# MotorControllerMainBoard.net
KiCad netlist of a schematic drawn in EAGLE
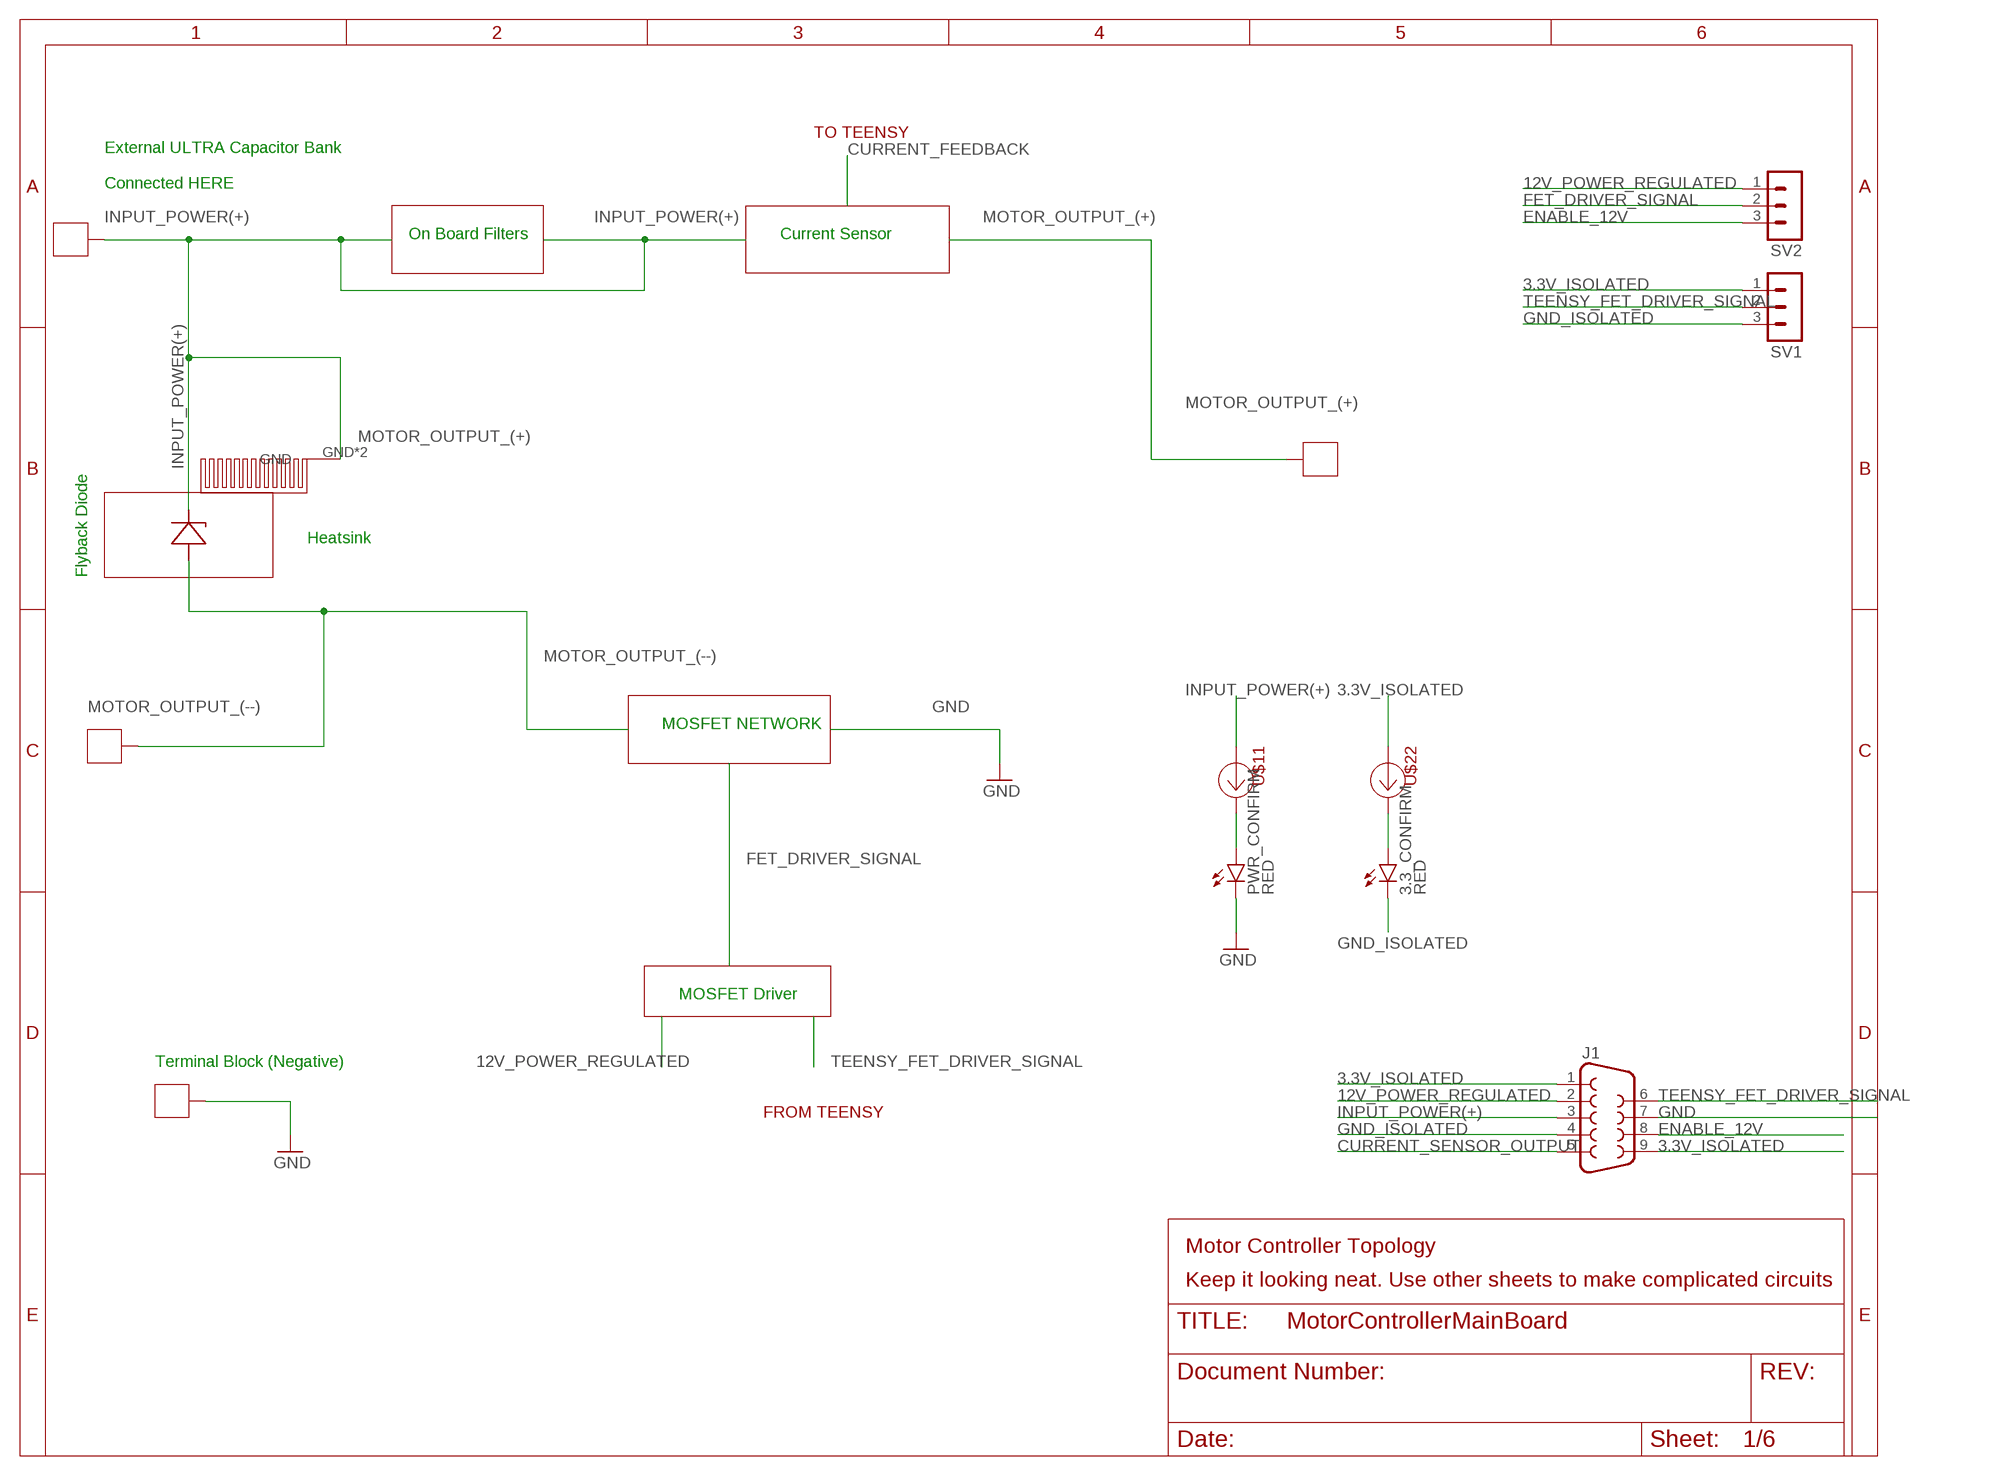
[diagram p0: schematic, sheet 1]
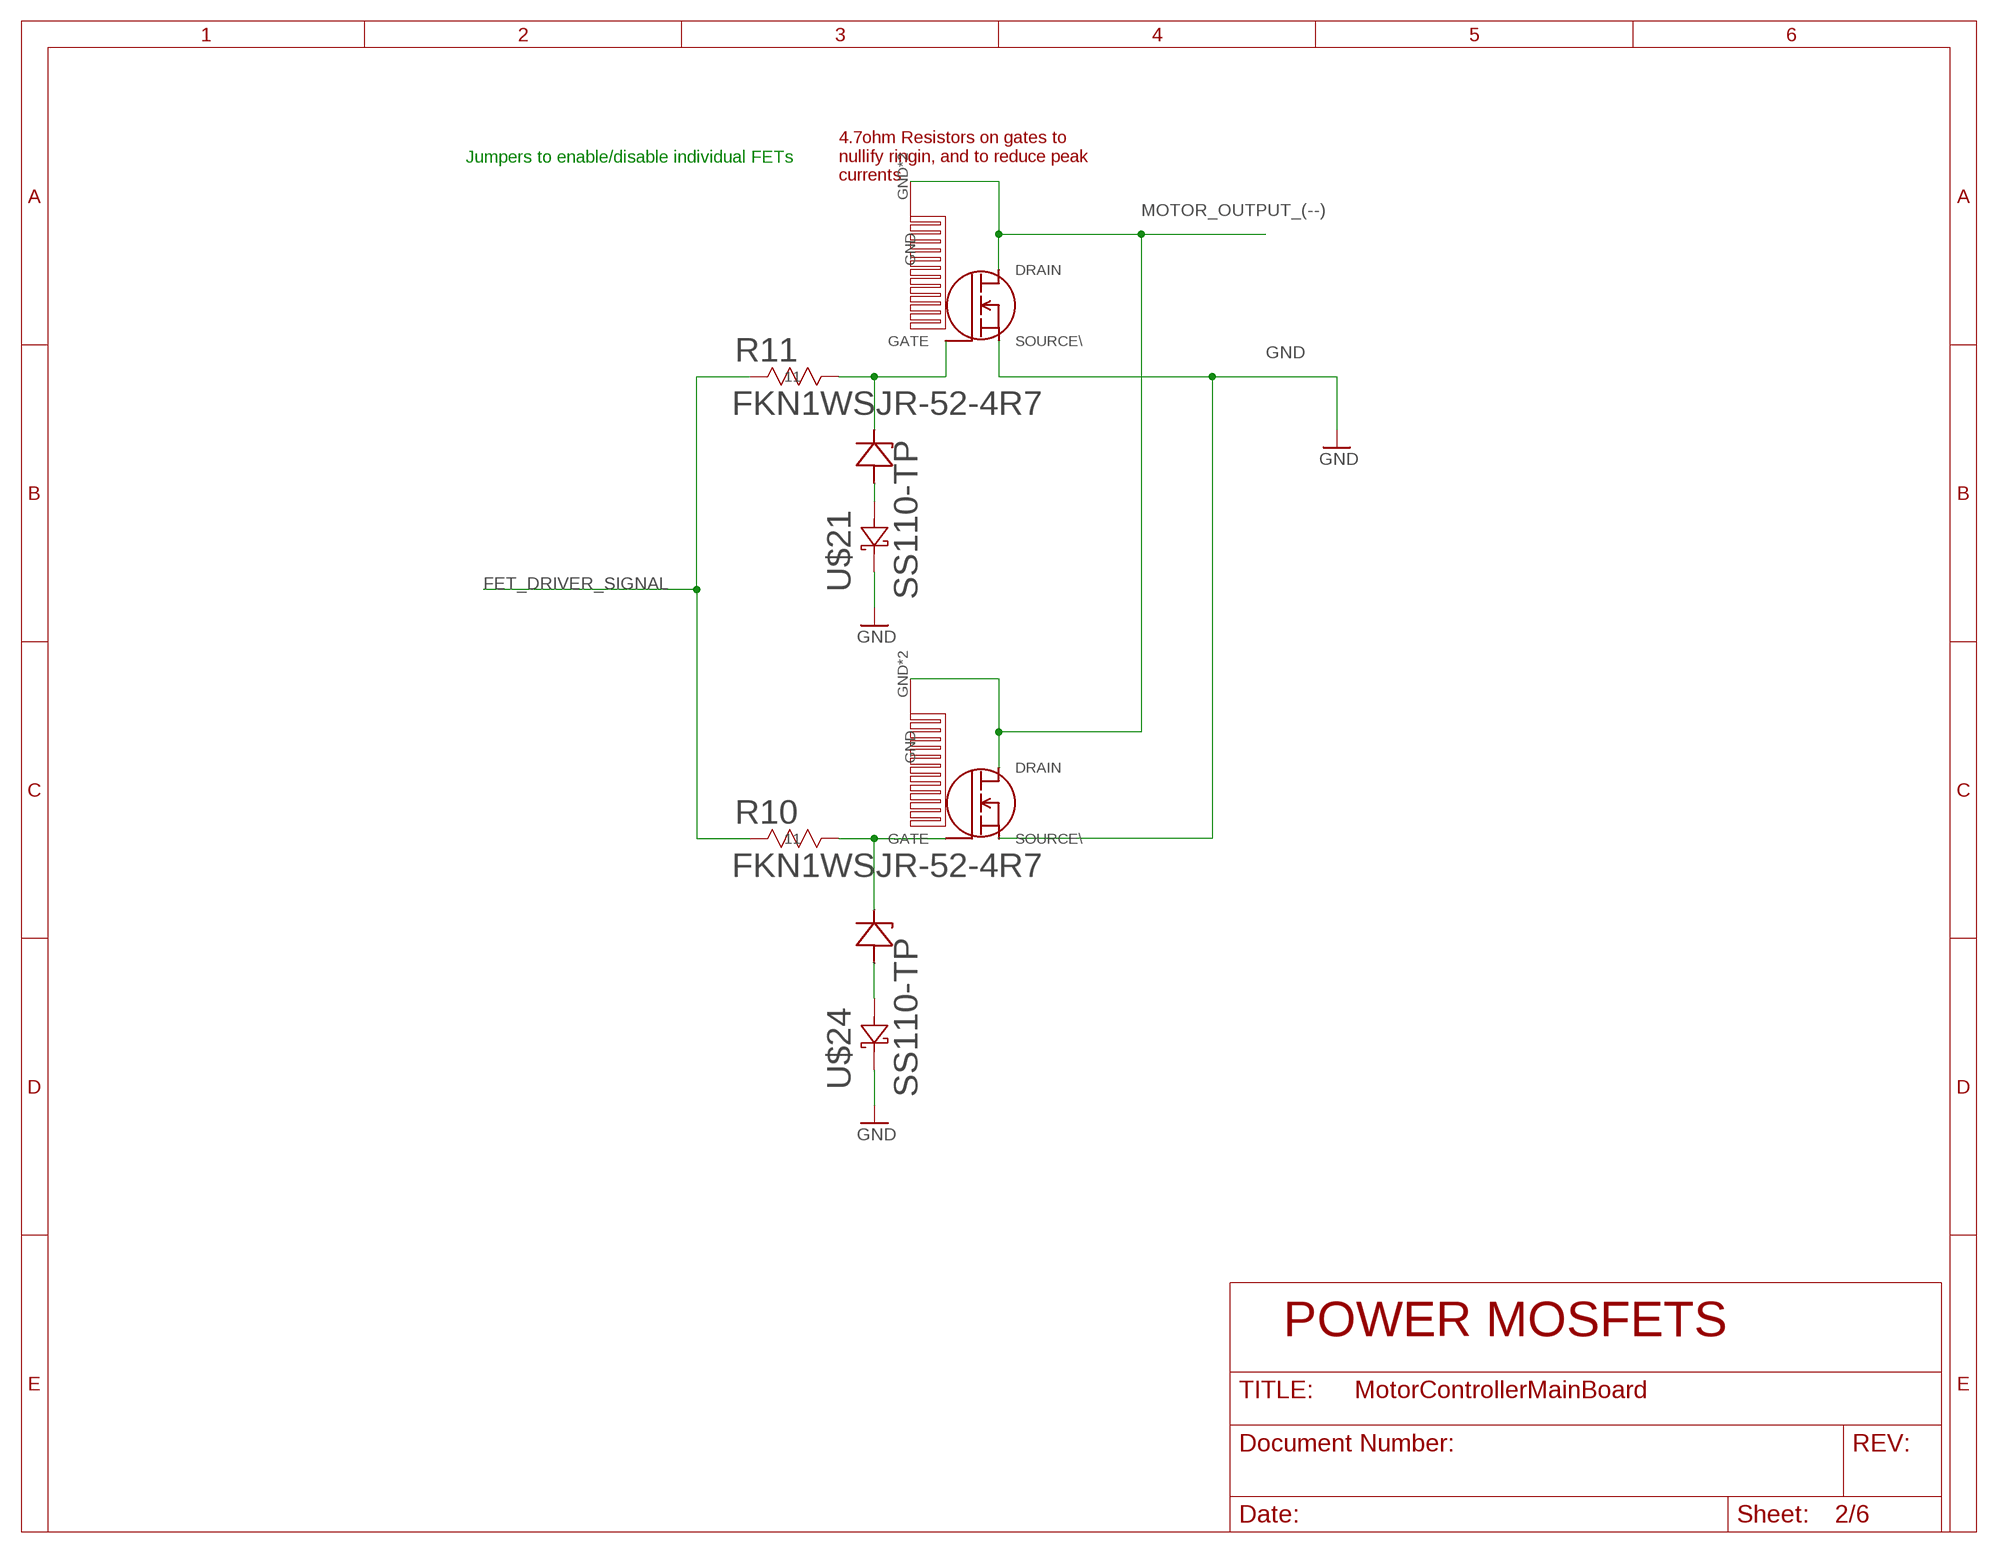
[diagram p1: schematic, sheet 2]
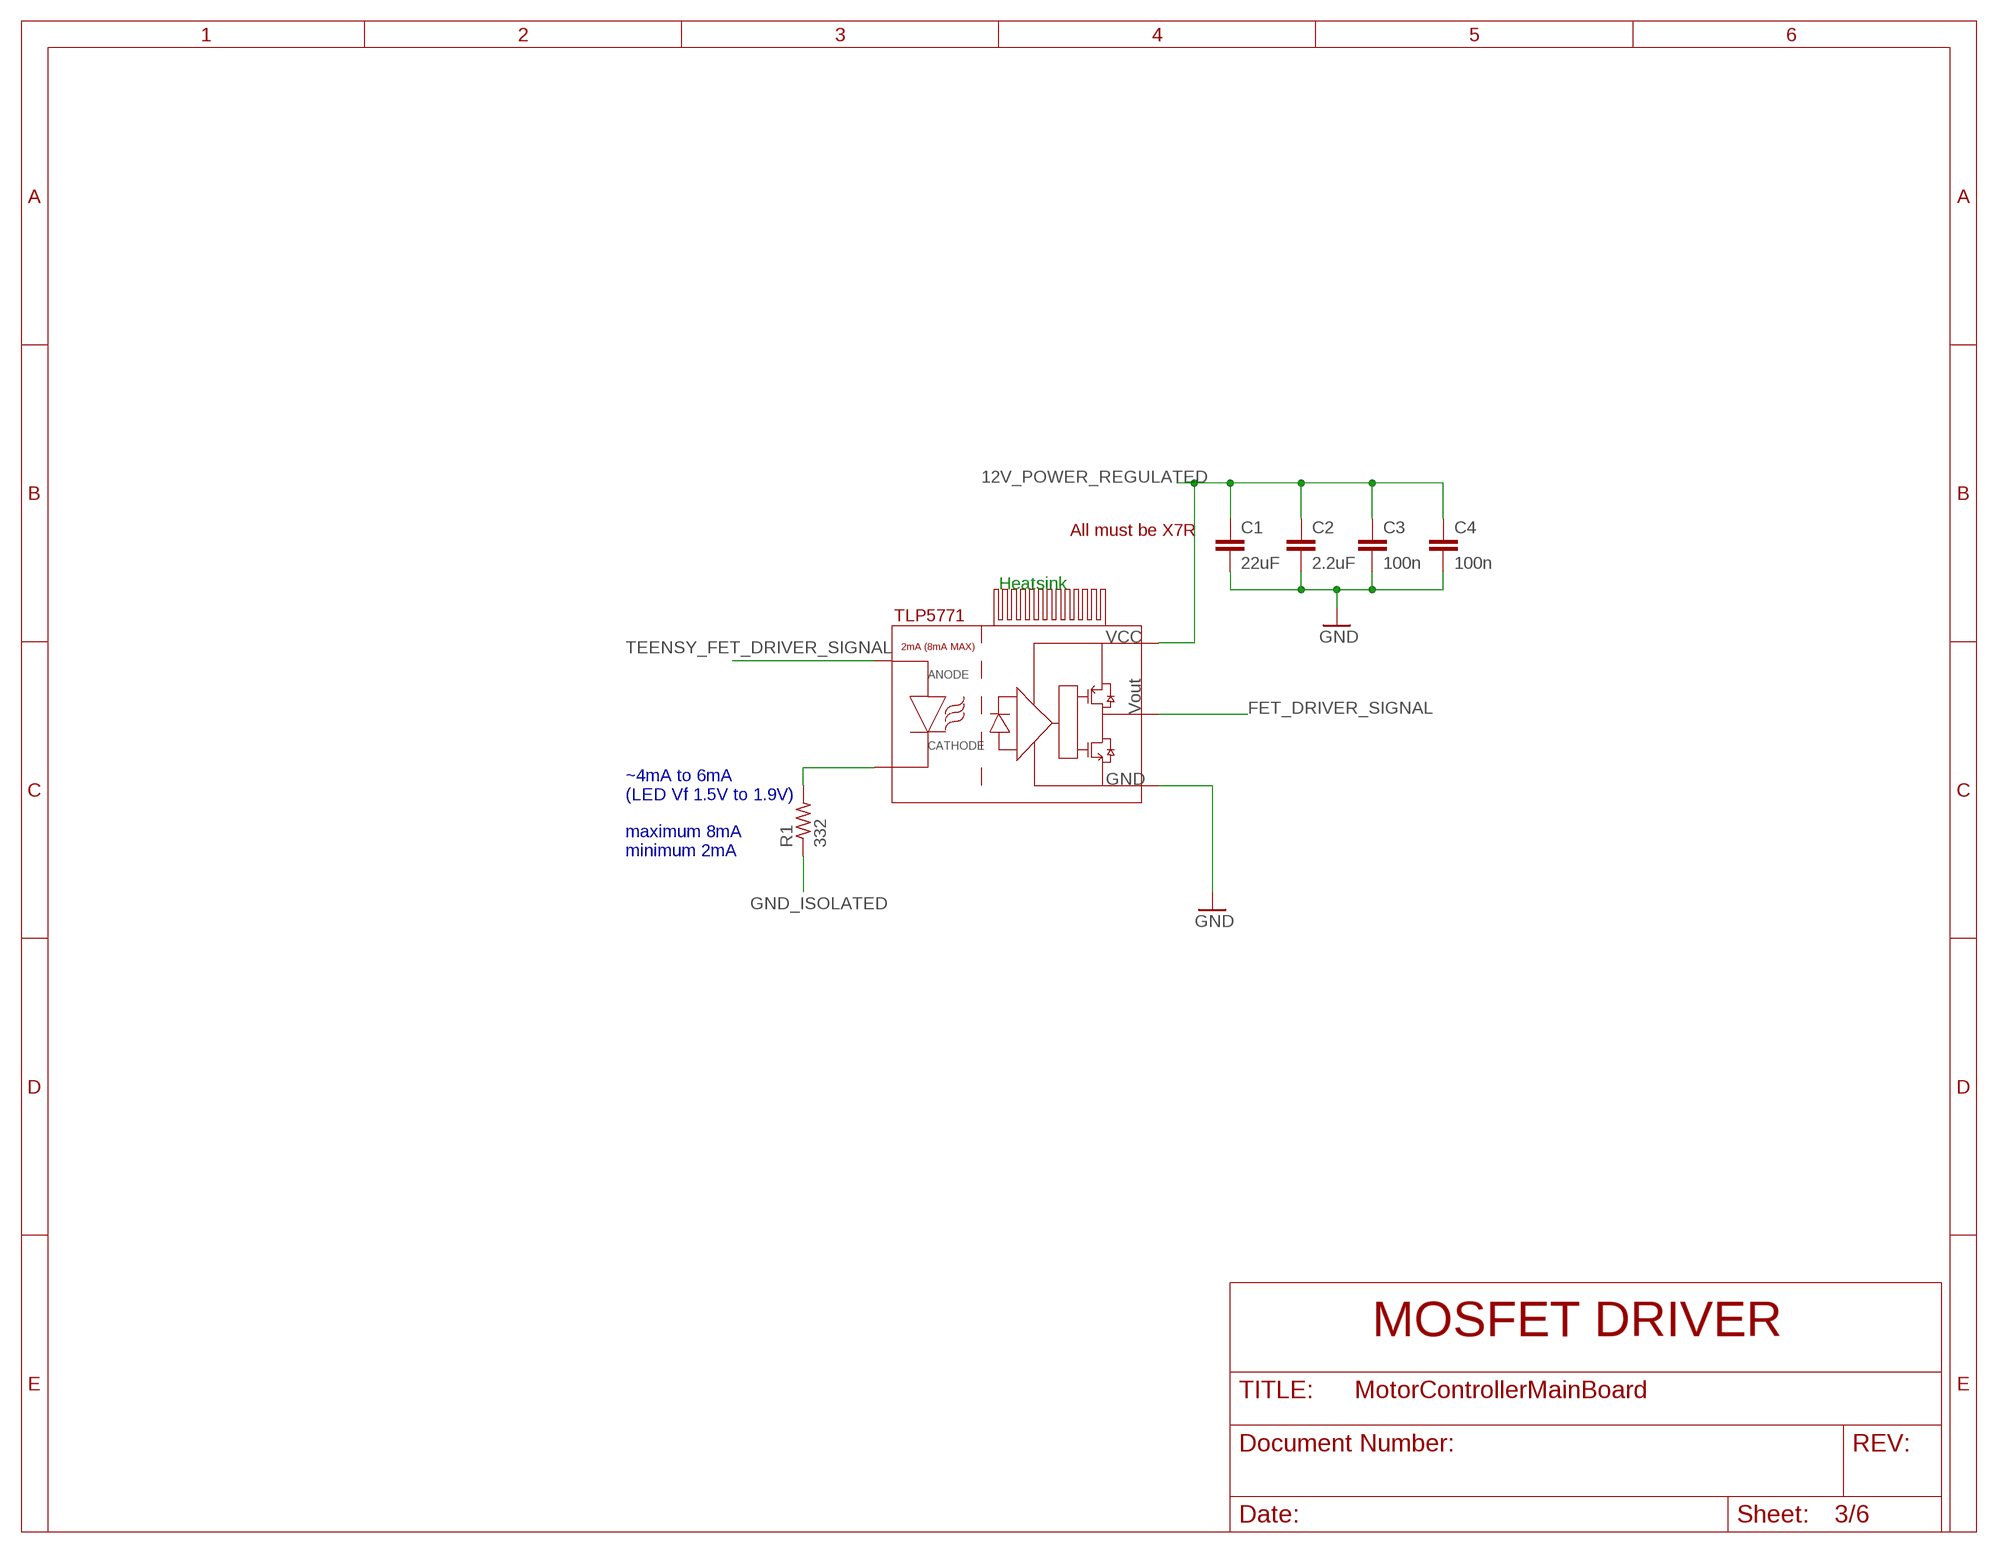
[diagram p2: schematic, sheet 3]
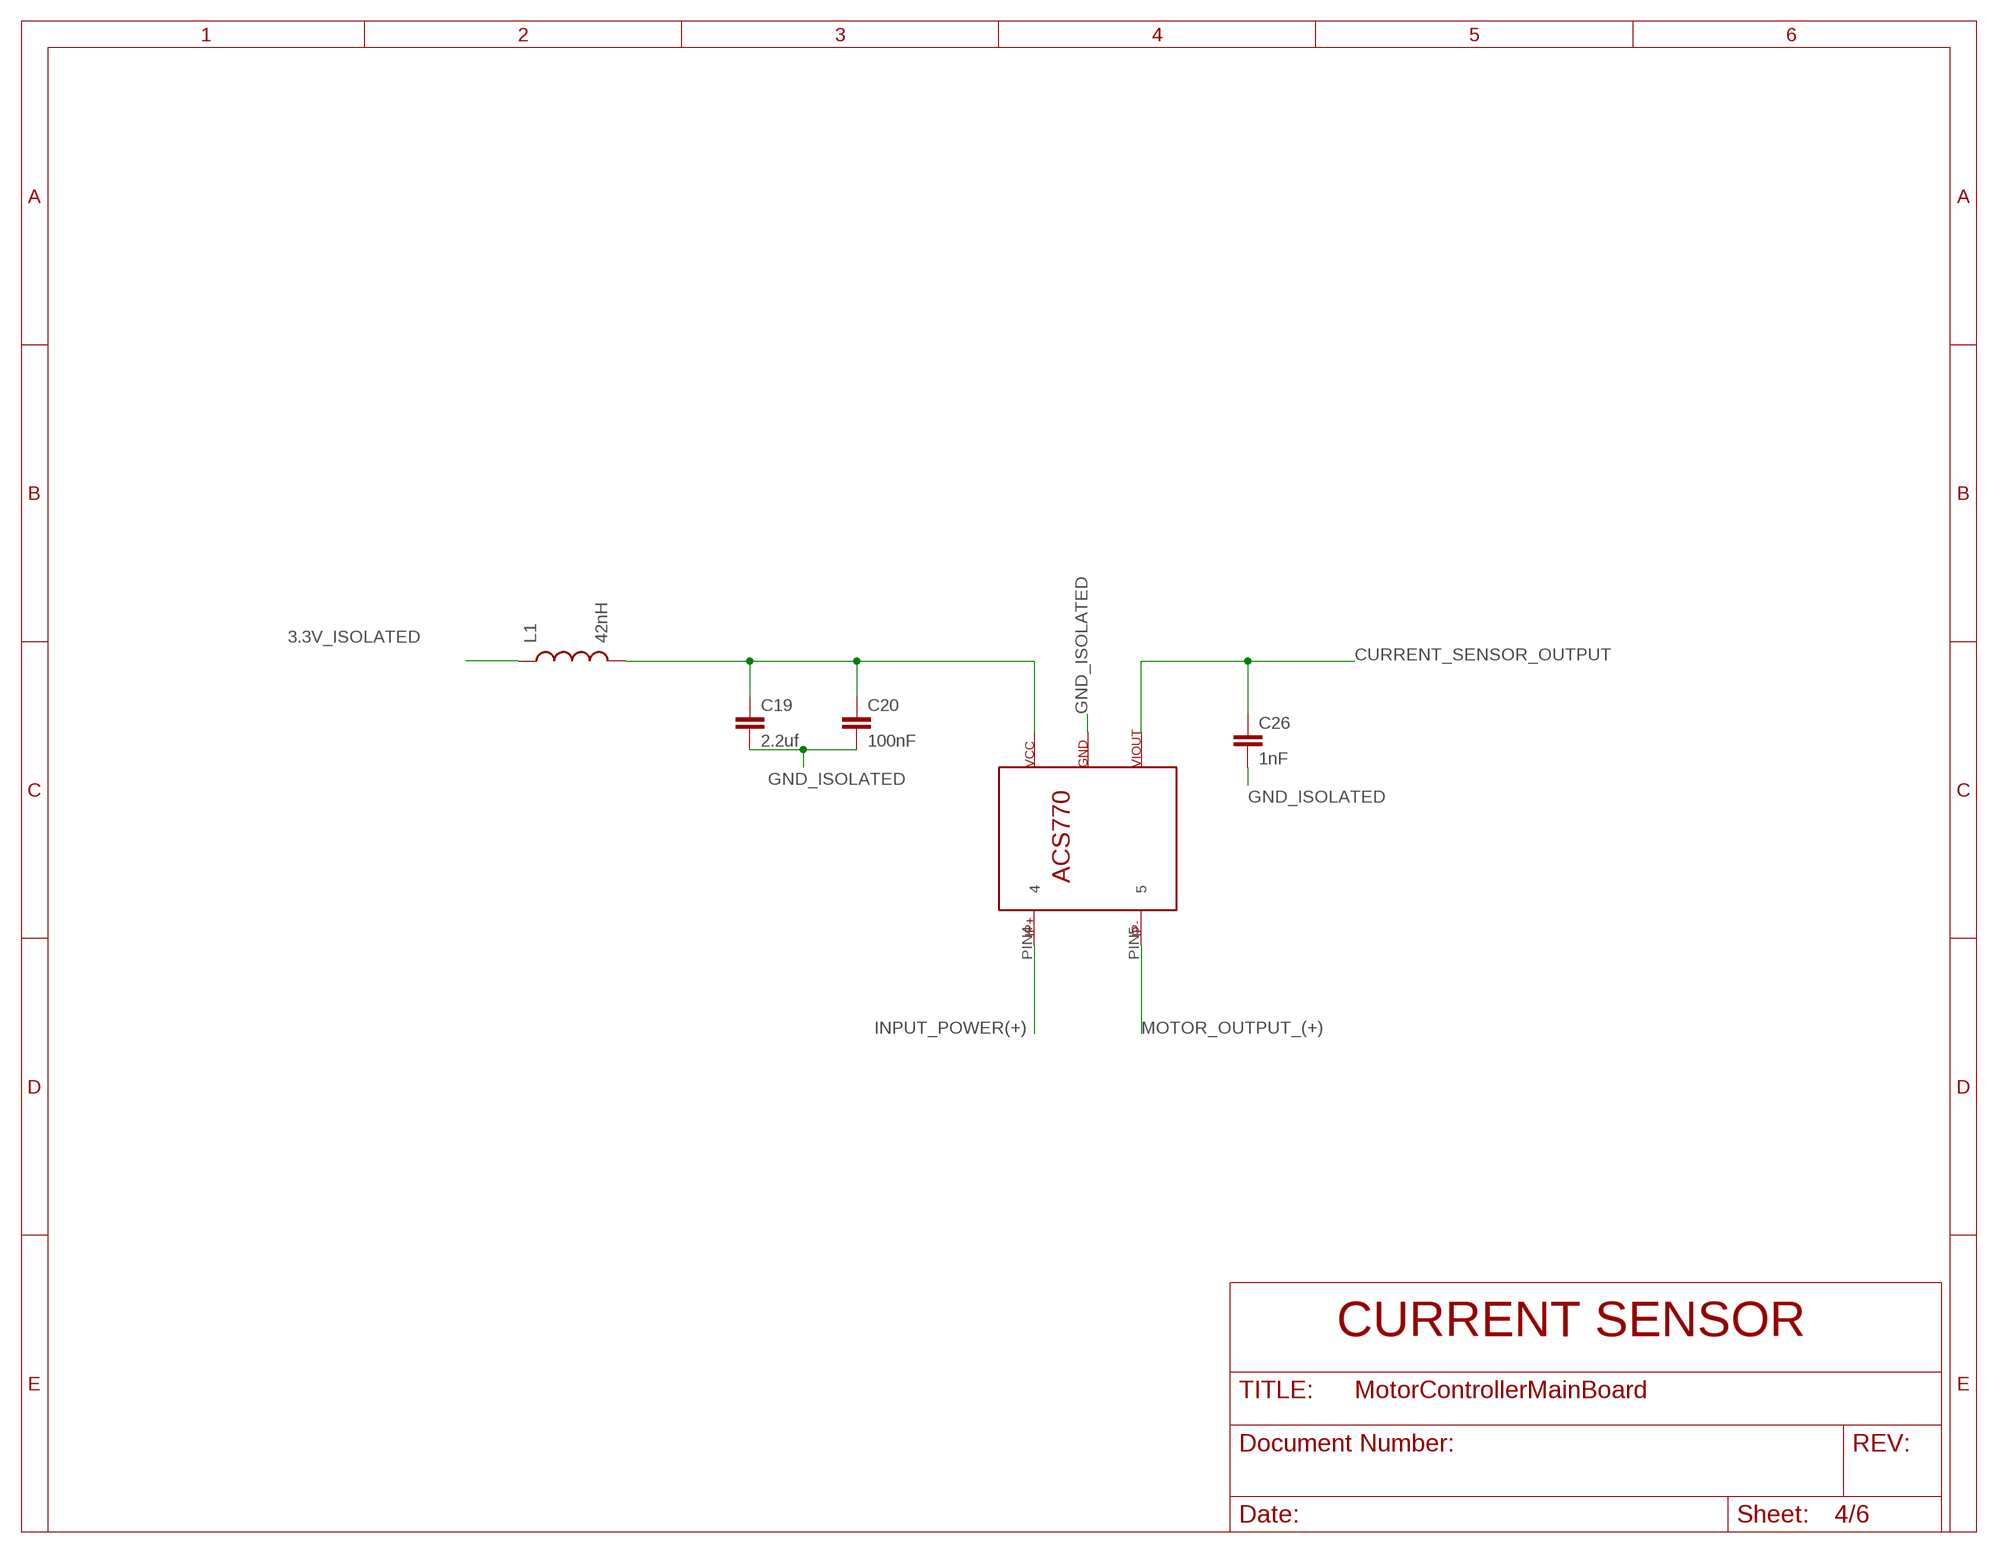
[diagram p3: schematic, sheet 4]
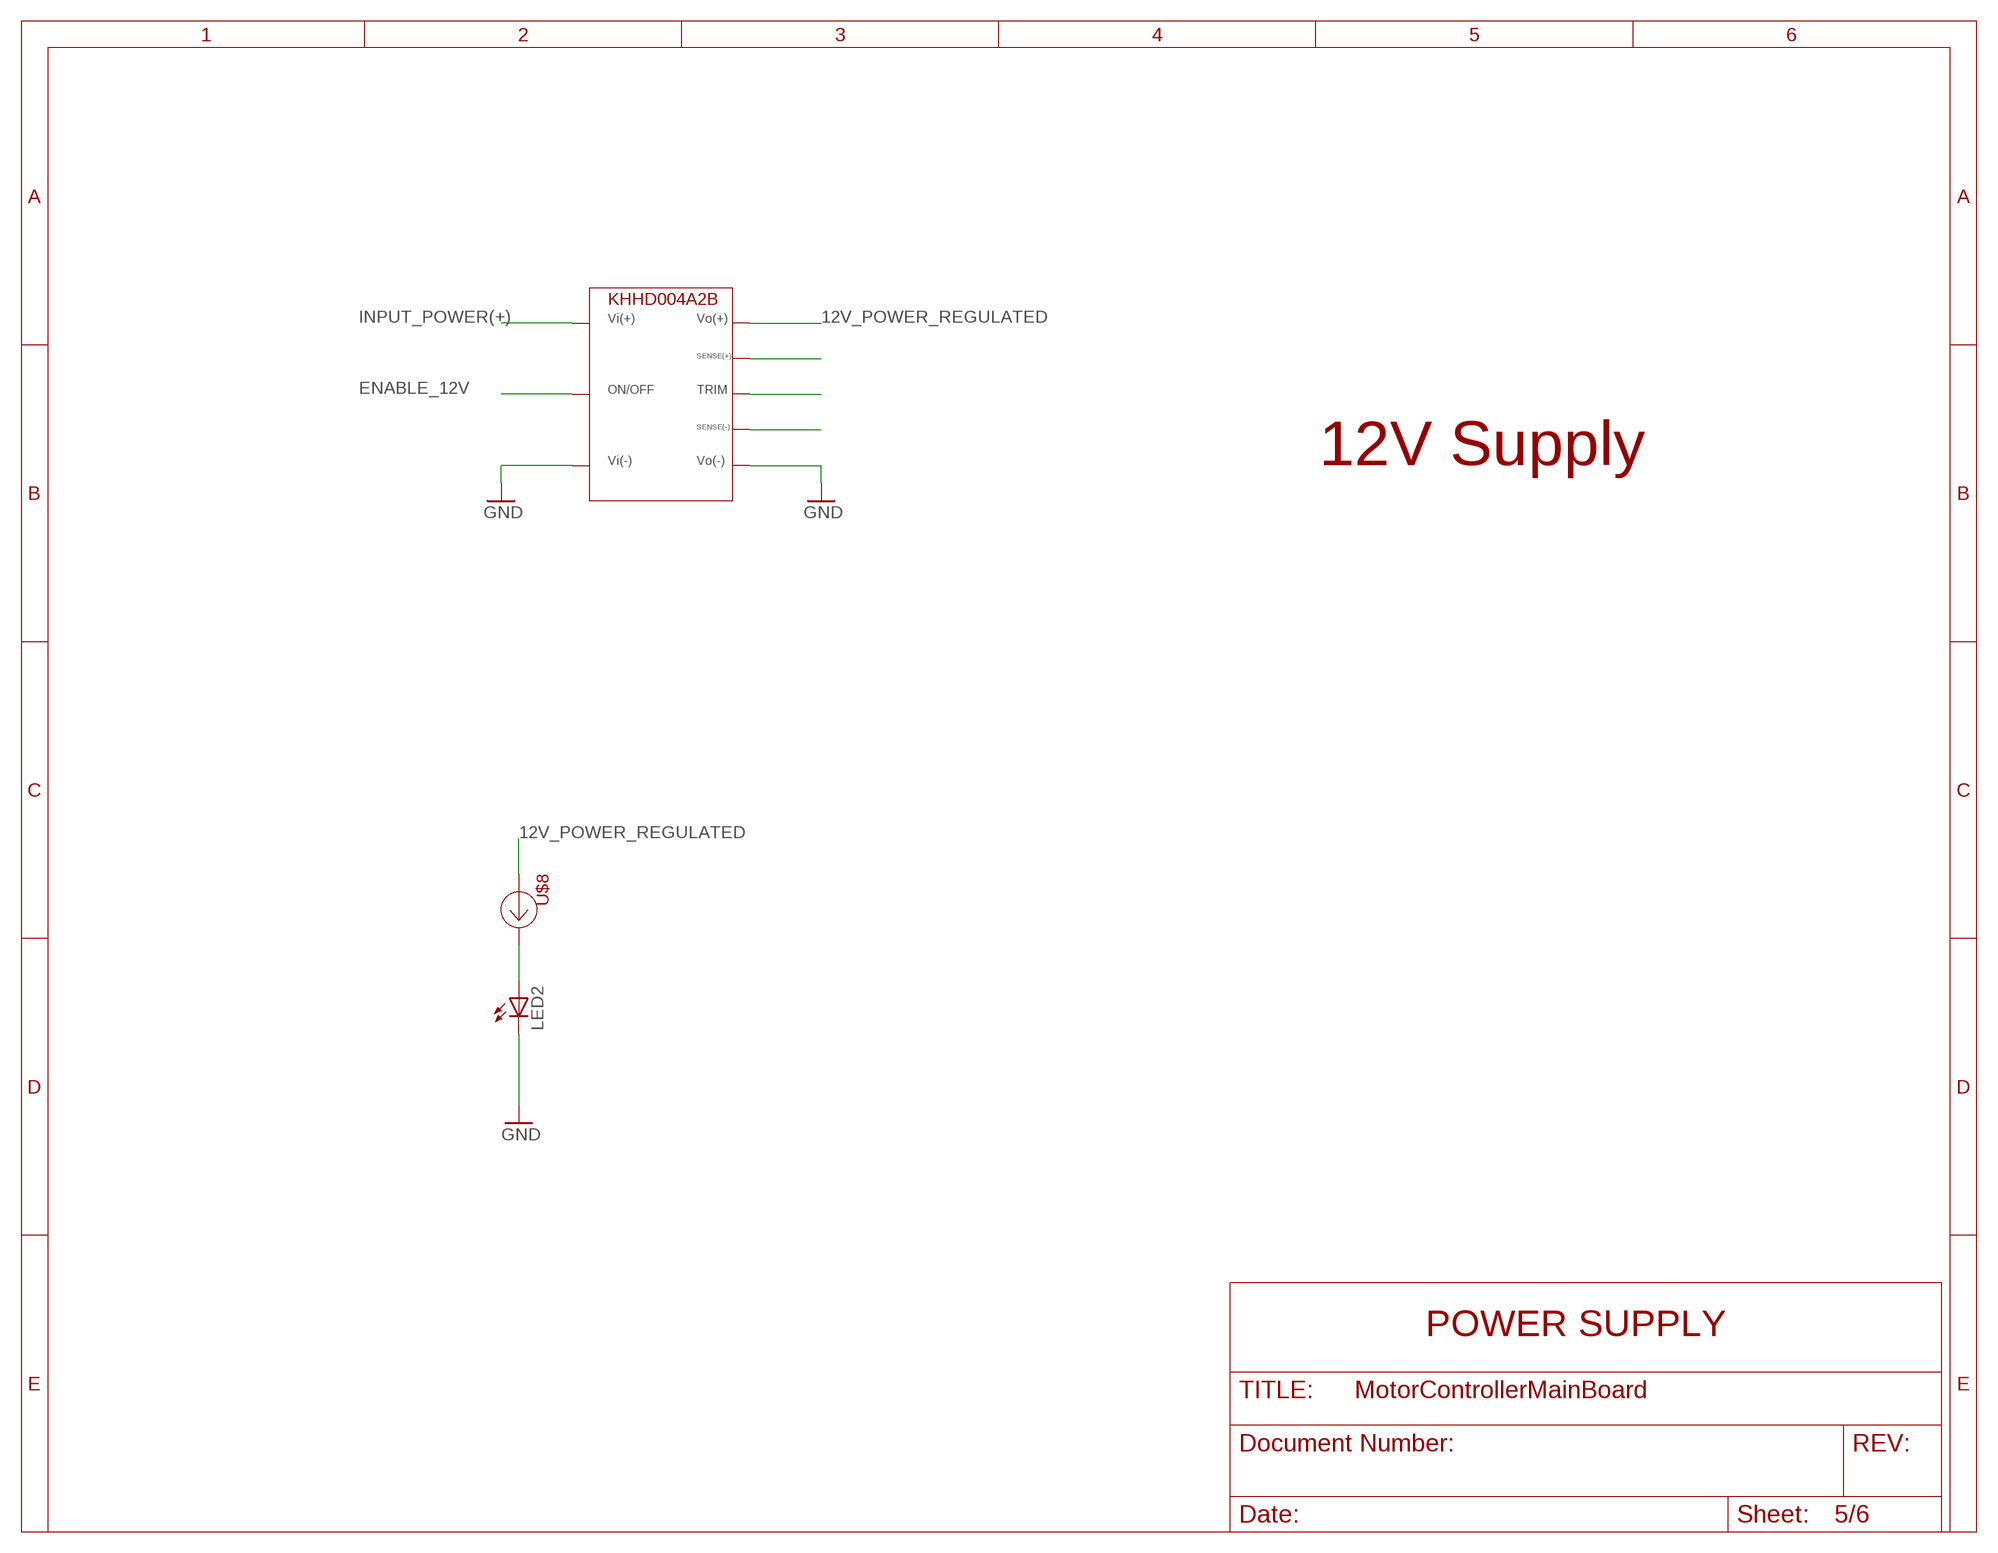
[diagram p4: schematic, sheet 5]
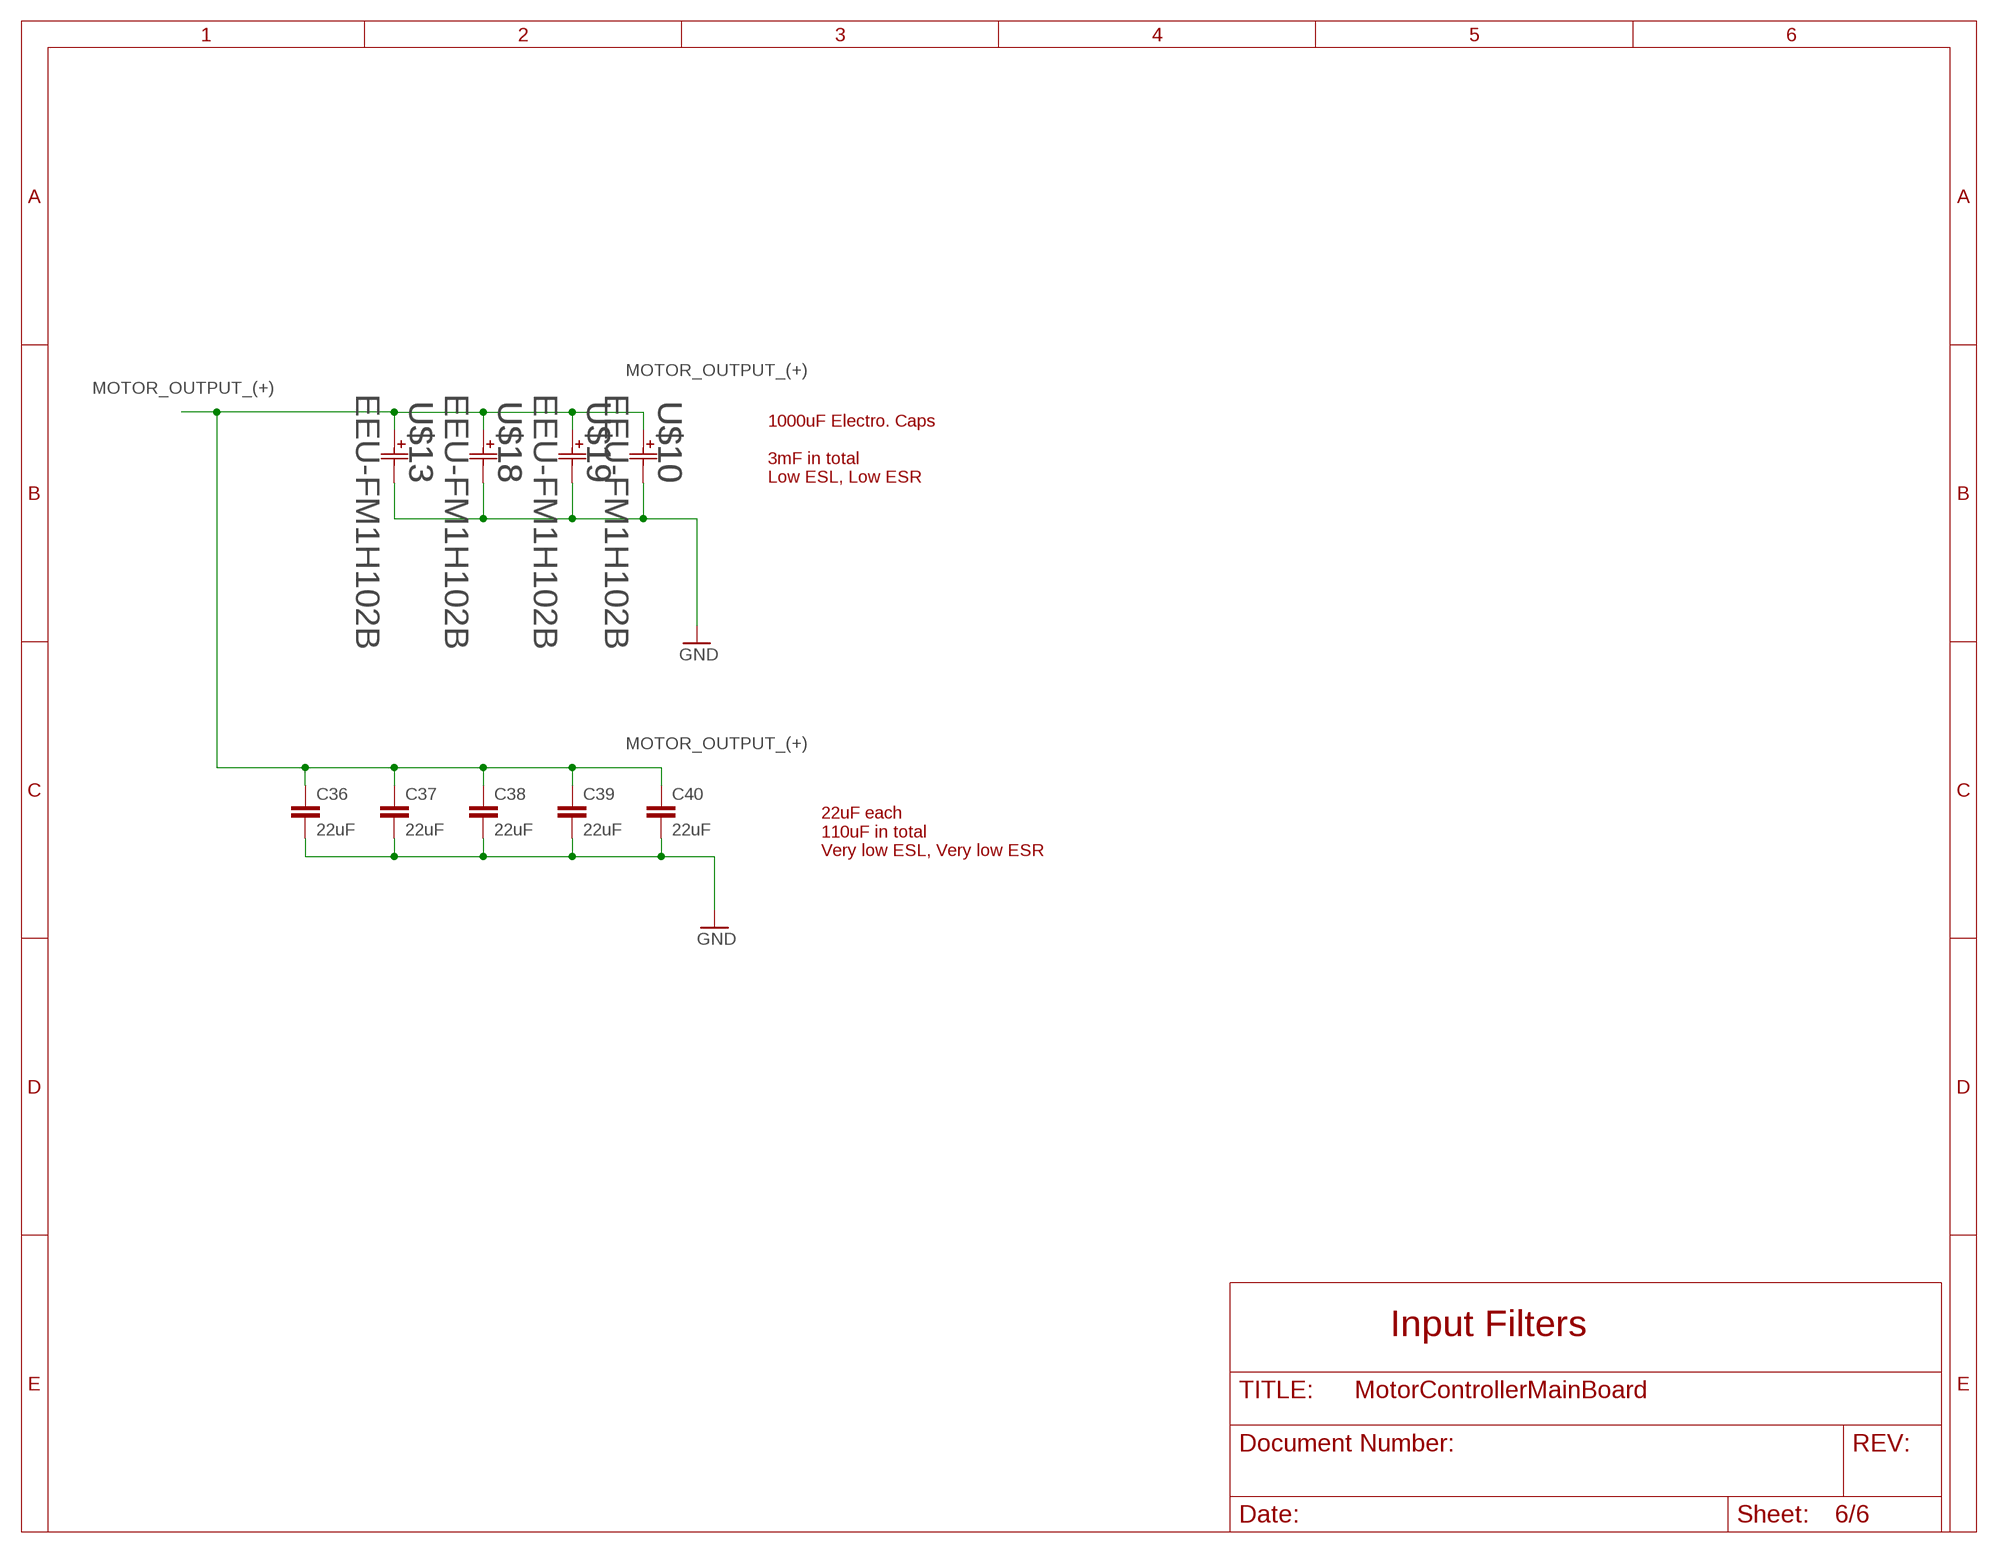
[diagram p5: schematic, sheet 6]

(export (version "E")
  (design (tool "Eeschema 10.0.6"))
  (components
    (comp (ref "3.3_CONFIRM")
      (value "RED")
      (footprint "eagle-import:LED-1206")
      (libsource (lib "eagle-import") (part "LED-RED1206"))
    )
    (comp (ref "J1")
      (value "DB9FEMALE")
      (footprint "eagle-import:DB9")
      (libsource (lib "eagle-import") (part "DB9FEMALE"))
    )
    (comp (ref "PWR_CONFIRM")
      (value "RED")
      (footprint "eagle-import:LED-1206")
      (libsource (lib "eagle-import") (part "LED-RED1206"))
    )
    (comp (ref "SV1")
      (value "MA03-1")
      (footprint "eagle-import:MA03-1")
      (libsource (lib "eagle-import") (part "MA03-1"))
    )
    (comp (ref "SV2")
      (value "MA03-1")
      (footprint "eagle-import:MA03-1")
      (libsource (lib "eagle-import") (part "MA03-1"))
    )
    (comp (ref "U$5")
      (value "FLYBACK")
      (footprint "eagle-import:TO")
      (libsource (lib "eagle-import") (part "FLYBACK"))
    )
    (comp (ref "U$11")
      (value "AL5809-20S1-7")
      (footprint "eagle-import:SOD-123")
      (libsource (lib "eagle-import") (part "AL5809-20S1-7"))
    )
    (comp (ref "U$12")
      (value "74650073R")
      (footprint "eagle-import:74650073R")
      (libsource (lib "eagle-import") (part "74650073R"))
    )
    (comp (ref "U$14")
      (value "74650073R")
      (footprint "eagle-import:74650073R")
      (libsource (lib "eagle-import") (part "74650073R"))
    )
    (comp (ref "U$15")
      (value "74650073R")
      (footprint "eagle-import:74650073R")
      (libsource (lib "eagle-import") (part "74650073R"))
    )
    (comp (ref "U$16")
      (value "74650073R")
      (footprint "eagle-import:74650073R")
      (libsource (lib "eagle-import") (part "74650073R"))
    )
    (comp (ref "U$22")
      (value "AL5809-20S1-7")
      (footprint "eagle-import:SOD-123")
      (libsource (lib "eagle-import") (part "AL5809-20S1-7"))
    )
    (comp (ref "U$23")
      (value "DA-T263-101E")
      (footprint "eagle-import:DA-T263-101E")
      (libsource (lib "eagle-import") (part "DA-T263-101E"))
    )
    (comp (ref "R10")
      (value "FKN1WSJR-52-4R7")
      (footprint "eagle-import:YAG_FKN50")
      (fields (field (name "MANUFACTURER_PART_NUMBER") "FKN1WSJR524R7"))
      (libsource (lib "eagle-import") (part "FKN1WSJR-52-4R7"))
    )
    (comp (ref "R11")
      (value "FKN1WSJR-52-4R7")
      (footprint "eagle-import:YAG_FKN50")
      (fields (field (name "MANUFACTURER_PART_NUMBER") "FKN1WSJR524R7"))
      (libsource (lib "eagle-import") (part "FKN1WSJR-52-4R7"))
    )
    (comp (ref "U$1")
      (value "IPB015N08N5ATMA1")
      (footprint "eagle-import:IPB015N08N5ATMA1")
      (libsource (lib "eagle-import") (part "IPB015N08N5ATMA1"))
    )
    (comp (ref "U$2")
      (value "IPB015N08N5ATMA1")
      (footprint "eagle-import:IPB015N08N5ATMA1")
      (libsource (lib "eagle-import") (part "IPB015N08N5ATMA1"))
    )
    (comp (ref "U$3")
      (value "DA-T263-101E")
      (footprint "eagle-import:DA-T263-101E")
      (libsource (lib "eagle-import") (part "DA-T263-101E"))
    )
    (comp (ref "U$4")
      (value "DA-T263-101E")
      (footprint "eagle-import:DA-T263-101E")
      (libsource (lib "eagle-import") (part "DA-T263-101E"))
    )
    (comp (ref "U$7")
      (value "SMBJ15CD")
      (footprint "eagle-import:SMB-DIODE")
      (libsource (lib "eagle-import") (part "SMBJ15CD"))
    )
    (comp (ref "U$20")
      (value "SMBJ15CD")
      (footprint "eagle-import:SMB-DIODE")
      (libsource (lib "eagle-import") (part "SMBJ15CD"))
    )
    (comp (ref "U$21")
      (value "SS110-TP")
      (footprint "eagle-import:SMA-DIODE")
      (libsource (lib "eagle-import") (part "SS110-TP"))
    )
    (comp (ref "U$24")
      (value "SS110-TP")
      (footprint "eagle-import:SMA-DIODE")
      (libsource (lib "eagle-import") (part "SS110-TP"))
    )
    (comp (ref "C19")
      (value "2.2uf")
      (footprint "eagle-import:C0805")
      (libsource (lib "eagle-import") (part "resistor_348_C-EUC0805"))
    )
    (comp (ref "C20")
      (value "100nF")
      (footprint "eagle-import:C0805")
      (libsource (lib "eagle-import") (part "resistor_348_C-EUC0805"))
    )
    (comp (ref "C26")
      (value "1nF")
      (footprint "eagle-import:C0805")
      (libsource (lib "eagle-import") (part "resistor_348_C-EUC0805"))
    )
    (comp (ref "L1")
      (value "42nH")
      (footprint "eagle-import:0805")
      (libsource (lib "eagle-import") (part "INDUCTOR0805"))
    )
    (comp (ref "U$9")
      (value "ACS770LCB_CURRENTSENSOR")
      (footprint "eagle-import:ACS770LCB_CURRENTSENSOR")
      (libsource (lib "eagle-import") (part "ACS770LCB_CURRENTSENSOR"))
    )
    (comp (ref "C36")
      (value "22uF")
      (footprint "eagle-import:C1210")
      (libsource (lib "eagle-import") (part "C-EUC1210"))
    )
    (comp (ref "C37")
      (value "22uF")
      (footprint "eagle-import:C1210")
      (libsource (lib "eagle-import") (part "C-EUC1210"))
    )
    (comp (ref "C38")
      (value "22uF")
      (footprint "eagle-import:C1210")
      (libsource (lib "eagle-import") (part "C-EUC1210"))
    )
    (comp (ref "C39")
      (value "22uF")
      (footprint "eagle-import:C1210")
      (libsource (lib "eagle-import") (part "C-EUC1210"))
    )
    (comp (ref "C40")
      (value "22uF")
      (footprint "eagle-import:C1210")
      (libsource (lib "eagle-import") (part "C-EUC1210"))
    )
    (comp (ref "U$10")
      (value "EEU-FM1H102B")
      (footprint "eagle-import:EEU-FM1H102B")
      (libsource (lib "eagle-import") (part "EEU-FM1H102B"))
    )
    (comp (ref "U$13")
      (value "EEU-FM1H102B")
      (footprint "eagle-import:EEU-FM1H102B")
      (libsource (lib "eagle-import") (part "EEU-FM1H102B"))
    )
    (comp (ref "U$18")
      (value "EEU-FM1H102B")
      (footprint "eagle-import:EEU-FM1H102B")
      (libsource (lib "eagle-import") (part "EEU-FM1H102B"))
    )
    (comp (ref "U$19")
      (value "EEU-FM1H102B")
      (footprint "eagle-import:EEU-FM1H102B")
      (libsource (lib "eagle-import") (part "EEU-FM1H102B"))
    )
    (comp (ref "C1")
      (value "22uF")
      (footprint "eagle-import:C1210")
      (libsource (lib "eagle-import") (part "C-EUC1210"))
    )
    (comp (ref "C2")
      (value "2.2uF")
      (footprint "eagle-import:C0805")
      (libsource (lib "eagle-import") (part "C-EUC0805"))
    )
    (comp (ref "C3")
      (value "100n")
      (footprint "eagle-import:C0603")
      (libsource (lib "eagle-import") (part "C-EUC0603"))
    )
    (comp (ref "C4")
      (value "100n")
      (footprint "eagle-import:C0603")
      (libsource (lib "eagle-import") (part "C-EUC0603"))
    )
    (comp (ref "R1")
      (value "332")
      (footprint "eagle-import:R0805")
      (libsource (lib "eagle-import") (part "R-US_R0805"))
    )
    (comp (ref "U$17")
      (value "TLP5771")
      (footprint "eagle-import:SOIC-6(TLP5771)")
      (libsource (lib "eagle-import") (part "TLP5771"))
    )
    (comp (ref "U$25")
      (value "LTN20069")
      (footprint "eagle-import:LTN20069")
      (libsource (lib "eagle-import") (part "LTN20069"))
    )
    (comp (ref "LED2")
      (value "LED1206")
      (footprint "eagle-import:LED-1206")
      (libsource (lib "eagle-import") (part "LED1206"))
    )
    (comp (ref "U$6")
      (value "KHHD004A2B")
      (footprint "eagle-import:KHHD004A2B")
      (libsource (lib "eagle-import") (part "KHHD004A2B"))
    )
    (comp (ref "U$8")
      (value "AL5809-20S1-7")
      (footprint "eagle-import:SOD-123")
      (libsource (lib "eagle-import") (part "AL5809-20S1-7"))
    )
  )
  (nets
    (net (code "1") (name "3.3V_ISOLATED") (class "Default")
      (node (ref "J1") (pin "1") (pinfunction "1_1") (pintype "passive"))
      (node (ref "J1") (pin "9") (pinfunction "9_9") (pintype "passive"))
      (node (ref "L1") (pin "1") (pinfunction "1_1") (pintype "passive"))
      (node (ref "SV1") (pin "1") (pinfunction "1_1") (pintype "passive"))
      (node (ref "U$22") (pin "A") (pinfunction "A_A") (pintype "bidirectional"))
    )
    (net (code "2") (name "12V_POWER_REGULATED") (class "Default")
      (node (ref "C1") (pin "1") (pinfunction "1_1") (pintype "passive"))
      (node (ref "C2") (pin "1") (pinfunction "1_1") (pintype "passive"))
      (node (ref "C3") (pin "1") (pinfunction "1_1") (pintype "passive"))
      (node (ref "C4") (pin "1") (pinfunction "1_1") (pintype "passive"))
      (node (ref "J1") (pin "2") (pinfunction "2_2") (pintype "passive"))
      (node (ref "SV2") (pin "1") (pinfunction "1_1") (pintype "passive"))
      (node (ref "U$17") (pin "6.VCC") (pinfunction "6.VCC_6.VCC") (pintype "bidirectional"))
      (node (ref "U$6") (pin "VO+") (pinfunction "VO(+)_VO+") (pintype "bidirectional"))
      (node (ref "U$8") (pin "A") (pinfunction "A_A") (pintype "bidirectional"))
    )
    (net (code "4") (name "CURRENT_SENSOR_OUTPUT") (class "Default")
      (node (ref "C26") (pin "1") (pinfunction "1_1") (pintype "passive"))
      (node (ref "J1") (pin "5") (pinfunction "5_5") (pintype "passive"))
      (node (ref "U$9") (pin "PIN3") (pinfunction "3_PIN3") (pintype "bidirectional"))
    )
    (net (code "5") (name "ENABLE_12V") (class "Default")
      (node (ref "J1") (pin "8") (pinfunction "8_8") (pintype "passive"))
      (node (ref "SV2") (pin "3") (pinfunction "3_3") (pintype "passive"))
      (node (ref "U$6") (pin "ON/OFF") (pinfunction "ON/OFF_ON/OFF") (pintype "bidirectional"))
    )
    (net (code "6") (name "FET_DRIVER_SIGNAL") (class "Default")
      (node (ref "R10") (pin "1") (pinfunction "11_1") (pintype "passive"))
      (node (ref "R11") (pin "1") (pinfunction "11_1") (pintype "passive"))
      (node (ref "SV2") (pin "2") (pinfunction "2_2") (pintype "passive"))
      (node (ref "U$17") (pin "5.VOUT") (pinfunction "5.VOUT_5.VOUT") (pintype "bidirectional"))
    )
    (net (code "7") (name "GND") (class "Default")
      (node (ref "C1") (pin "2") (pinfunction "2_2") (pintype "passive"))
      (node (ref "C2") (pin "2") (pinfunction "2_2") (pintype "passive"))
      (node (ref "C3") (pin "2") (pinfunction "2_2") (pintype "passive"))
      (node (ref "C36") (pin "2") (pinfunction "2_2") (pintype "passive"))
      (node (ref "C37") (pin "2") (pinfunction "2_2") (pintype "passive"))
      (node (ref "C38") (pin "2") (pinfunction "2_2") (pintype "passive"))
      (node (ref "C39") (pin "2") (pinfunction "2_2") (pintype "passive"))
      (node (ref "C4") (pin "2") (pinfunction "2_2") (pintype "passive"))
      (node (ref "C40") (pin "2") (pinfunction "2_2") (pintype "passive"))
      (node (ref "J1") (pin "7") (pinfunction "7_7") (pintype "passive"))
      (node (ref "LED2") (pin "C") (pinfunction "C_C") (pintype "passive"))
      (node (ref "PWR_CONFIRM") (pin "C") (pinfunction "C_C") (pintype "passive"))
      (node (ref "U$1") (pin "SOURCE") (pinfunction "SOURCE\\_SOURCE") (pintype "bidirectional"))
      (node (ref "U$10") (pin "NEGATIVE") (pinfunction "NEGATIVE_NEGATIVE") (pintype "passive"))
      (node (ref "U$13") (pin "NEGATIVE") (pinfunction "NEGATIVE_NEGATIVE") (pintype "passive"))
      (node (ref "U$15") (pin "P$1") (pinfunction "P$1_P$1") (pintype "bidirectional"))
      (node (ref "U$15") (pin "P$2") (pinfunction "P$1_P$2") (pintype "bidirectional"))
      (node (ref "U$15") (pin "P$3") (pinfunction "P$1_P$3") (pintype "bidirectional"))
      (node (ref "U$15") (pin "P$4") (pinfunction "P$1_P$4") (pintype "bidirectional"))
      (node (ref "U$17") (pin "4.GND") (pinfunction "4.GND_4.GND") (pintype "bidirectional"))
      (node (ref "U$18") (pin "NEGATIVE") (pinfunction "NEGATIVE_NEGATIVE") (pintype "passive"))
      (node (ref "U$19") (pin "NEGATIVE") (pinfunction "NEGATIVE_NEGATIVE") (pintype "passive"))
      (node (ref "U$2") (pin "SOURCE") (pinfunction "SOURCE\\_SOURCE") (pintype "bidirectional"))
      (node (ref "U$21") (pin "C") (pinfunction "CATHODE_C") (pintype "passive"))
      (node (ref "U$24") (pin "C") (pinfunction "CATHODE_C") (pintype "passive"))
      (node (ref "U$6") (pin "VI-") (pinfunction "VI(-)_VI-") (pintype "bidirectional"))
      (node (ref "U$6") (pin "VO-") (pinfunction "VO(-)_VO-") (pintype "bidirectional"))
    )
    (net (code "8") (name "GND_ISOLATED") (class "Default")
      (node (ref "3.3_CONFIRM") (pin "C") (pinfunction "C_C") (pintype "passive"))
      (node (ref "C19") (pin "2") (pinfunction "2_2") (pintype "passive"))
      (node (ref "C20") (pin "2") (pinfunction "2_2") (pintype "passive"))
      (node (ref "C26") (pin "2") (pinfunction "2_2") (pintype "passive"))
      (node (ref "J1") (pin "4") (pinfunction "4_4") (pintype "passive"))
      (node (ref "R1") (pin "1") (pinfunction "1_1") (pintype "passive"))
      (node (ref "SV1") (pin "3") (pinfunction "3_3") (pintype "passive"))
      (node (ref "U$9") (pin "PIN2") (pinfunction "2_PIN2") (pintype "bidirectional"))
    )
    (net (code "9") (name "INPUT_POWER(+)") (class "Default")
      (node (ref "J1") (pin "3") (pinfunction "3_3") (pintype "passive"))
      (node (ref "U$11") (pin "A") (pinfunction "A_A") (pintype "bidirectional"))
      (node (ref "U$14") (pin "P$1") (pinfunction "P$1_P$1") (pintype "bidirectional"))
      (node (ref "U$14") (pin "P$2") (pinfunction "P$1_P$2") (pintype "bidirectional"))
      (node (ref "U$14") (pin "P$3") (pinfunction "P$1_P$3") (pintype "bidirectional"))
      (node (ref "U$14") (pin "P$4") (pinfunction "P$1_P$4") (pintype "bidirectional"))
      (node (ref "U$23") (pin "GND") (pinfunction "GND_GND") (pintype "bidirectional"))
      (node (ref "U$23") (pin "GND2\\") (pinfunction "GND_GND2\\") (pintype "bidirectional"))
      (node (ref "U$5") (pin "CATHODE") (pinfunction "CATHODE_CATHODE") (pintype "bidirectional"))
      (node (ref "U$6") (pin "VI+") (pinfunction "VI(+)_VI+") (pintype "bidirectional"))
      (node (ref "U$9") (pin "PIN4") (pinfunction "4_PIN4") (pintype "bidirectional"))
    )
    (net (code "10") (name "MOTOR_OUTPUT_(+)") (class "Default")
      (node (ref "C36") (pin "1") (pinfunction "1_1") (pintype "passive"))
      (node (ref "C37") (pin "1") (pinfunction "1_1") (pintype "passive"))
      (node (ref "C38") (pin "1") (pinfunction "1_1") (pintype "passive"))
      (node (ref "C39") (pin "1") (pinfunction "1_1") (pintype "passive"))
      (node (ref "C40") (pin "1") (pinfunction "1_1") (pintype "passive"))
      (node (ref "U$10") (pin "POSITIVE") (pinfunction "POSITIVE_POSITIVE") (pintype "passive"))
      (node (ref "U$13") (pin "POSITIVE") (pinfunction "POSITIVE_POSITIVE") (pintype "passive"))
      (node (ref "U$16") (pin "P$1") (pinfunction "P$1_P$1") (pintype "bidirectional"))
      (node (ref "U$16") (pin "P$2") (pinfunction "P$1_P$2") (pintype "bidirectional"))
      (node (ref "U$16") (pin "P$3") (pinfunction "P$1_P$3") (pintype "bidirectional"))
      (node (ref "U$16") (pin "P$4") (pinfunction "P$1_P$4") (pintype "bidirectional"))
      (node (ref "U$18") (pin "POSITIVE") (pinfunction "POSITIVE_POSITIVE") (pintype "passive"))
      (node (ref "U$19") (pin "POSITIVE") (pinfunction "POSITIVE_POSITIVE") (pintype "passive"))
      (node (ref "U$9") (pin "PIN5") (pinfunction "5_PIN5") (pintype "bidirectional"))
    )
    (net (code "11") (name "MOTOR_OUTPUT_(--)") (class "Default")
      (node (ref "U$1") (pin "DRAIN") (pinfunction "DRAIN_DRAIN") (pintype "bidirectional"))
      (node (ref "U$12") (pin "P$1") (pinfunction "P$1_P$1") (pintype "bidirectional"))
      (node (ref "U$12") (pin "P$2") (pinfunction "P$1_P$2") (pintype "bidirectional"))
      (node (ref "U$12") (pin "P$3") (pinfunction "P$1_P$3") (pintype "bidirectional"))
      (node (ref "U$12") (pin "P$4") (pinfunction "P$1_P$4") (pintype "bidirectional"))
      (node (ref "U$2") (pin "DRAIN") (pinfunction "DRAIN_DRAIN") (pintype "bidirectional"))
      (node (ref "U$3") (pin "GND") (pinfunction "GND_GND") (pintype "bidirectional"))
      (node (ref "U$3") (pin "GND2\\") (pinfunction "GND_GND2\\") (pintype "bidirectional"))
      (node (ref "U$4") (pin "GND") (pinfunction "GND_GND") (pintype "bidirectional"))
      (node (ref "U$4") (pin "GND2\\") (pinfunction "GND_GND2\\") (pintype "bidirectional"))
      (node (ref "U$5") (pin "ANODE") (pinfunction "ANODE_ANODE") (pintype "bidirectional"))
    )
    (net (code "12") (name "Net-(3.3_CONFIRM-PadA)") (class "Default")
      (node (ref "3.3_CONFIRM") (pin "A") (pinfunction "A_A") (pintype "passive"))
      (node (ref "U$22") (pin "C") (pinfunction "C_C") (pintype "bidirectional"))
    )
    (net (code "13") (name "Net-(LED2-PadA)") (class "Default")
      (node (ref "LED2") (pin "A") (pinfunction "A_A") (pintype "passive"))
      (node (ref "U$8") (pin "C") (pinfunction "C_C") (pintype "bidirectional"))
    )
    (net (code "14") (name "Net-(PWR_CONFIRM-PadA)") (class "Default")
      (node (ref "PWR_CONFIRM") (pin "A") (pinfunction "A_A") (pintype "passive"))
      (node (ref "U$11") (pin "C") (pinfunction "C_C") (pintype "bidirectional"))
    )
    (net (code "15") (name "Net-(R1-Pad2)") (class "Default")
      (node (ref "R1") (pin "2") (pinfunction "2_2") (pintype "passive"))
      (node (ref "U$17") (pin "2.NC") (pinfunction "3.CATHODE_2.NC") (pintype "bidirectional"))
      (node (ref "U$17") (pin "3:CATHODE") (pinfunction "3.CATHODE_3:CATHODE") (pintype "bidirectional"))
    )
    (net (code "16") (name "Net-(R10-22)") (class "Default")
      (node (ref "R10") (pin "2") (pinfunction "22_2") (pintype "passive"))
      (node (ref "U$2") (pin "GATE") (pinfunction "GATE_GATE") (pintype "bidirectional"))
      (node (ref "U$7") (pin "C") (pinfunction "CATHODE_C") (pintype "bidirectional"))
    )
    (net (code "17") (name "Net-(R11-22)") (class "Default")
      (node (ref "R11") (pin "2") (pinfunction "22_2") (pintype "passive"))
      (node (ref "U$1") (pin "GATE") (pinfunction "GATE_GATE") (pintype "bidirectional"))
      (node (ref "U$20") (pin "C") (pinfunction "CATHODE_C") (pintype "bidirectional"))
    )
    (net (code "18") (name "Net-(U$9-1)") (class "Default")
      (node (ref "C19") (pin "1") (pinfunction "1_1") (pintype "passive"))
      (node (ref "C20") (pin "1") (pinfunction "1_1") (pintype "passive"))
      (node (ref "L1") (pin "2") (pinfunction "2_2") (pintype "passive"))
      (node (ref "U$9") (pin "PIN1") (pinfunction "1_PIN1") (pintype "bidirectional"))
    )
    (net (code "19") (name "Net-(U$20-ANODE)") (class "Default")
      (node (ref "U$20") (pin "A") (pinfunction "ANODE_A") (pintype "bidirectional"))
      (node (ref "U$21") (pin "A") (pinfunction "ANODE_A") (pintype "passive"))
    )
    (net (code "20") (name "Net-(U$24-ANODE)") (class "Default")
      (node (ref "U$24") (pin "A") (pinfunction "ANODE_A") (pintype "passive"))
      (node (ref "U$7") (pin "A") (pinfunction "ANODE_A") (pintype "bidirectional"))
    )
    (net (code "21") (name "TEENSY_FET_DRIVER_SIGNAL") (class "Default")
      (node (ref "J1") (pin "6") (pinfunction "6_6") (pintype "passive"))
      (node (ref "SV1") (pin "2") (pinfunction "2_2") (pintype "passive"))
      (node (ref "U$17") (pin "1.ANODE") (pinfunction "1.ANODE_1.ANODE") (pintype "bidirectional"))
    )
    (net (code "22") (name "unconnected-(U$6-PadTRIM)") (class "Default")
      (node (ref "U$6") (pin "TRIM") (pinfunction "TRIM_TRIM") (pintype "bidirectional"))
    )
    (net (code "23") (name "unconnected-(U$6-SENSE(+)-PadSENSE+)") (class "Default")
      (node (ref "U$6") (pin "SENSE+") (pinfunction "SENSE(+)_SENSE+") (pintype "bidirectional"))
    )
    (net (code "24") (name "unconnected-(U$6-SENSE(-)-PadSENSE-)") (class "Default")
      (node (ref "U$6") (pin "SENSE-") (pinfunction "SENSE(-)_SENSE-") (pintype "bidirectional"))
    )
  )
)
